# Hoja_principal_Sumo_2024.net
KiCad netlist of a schematic drawn in Altium Designer
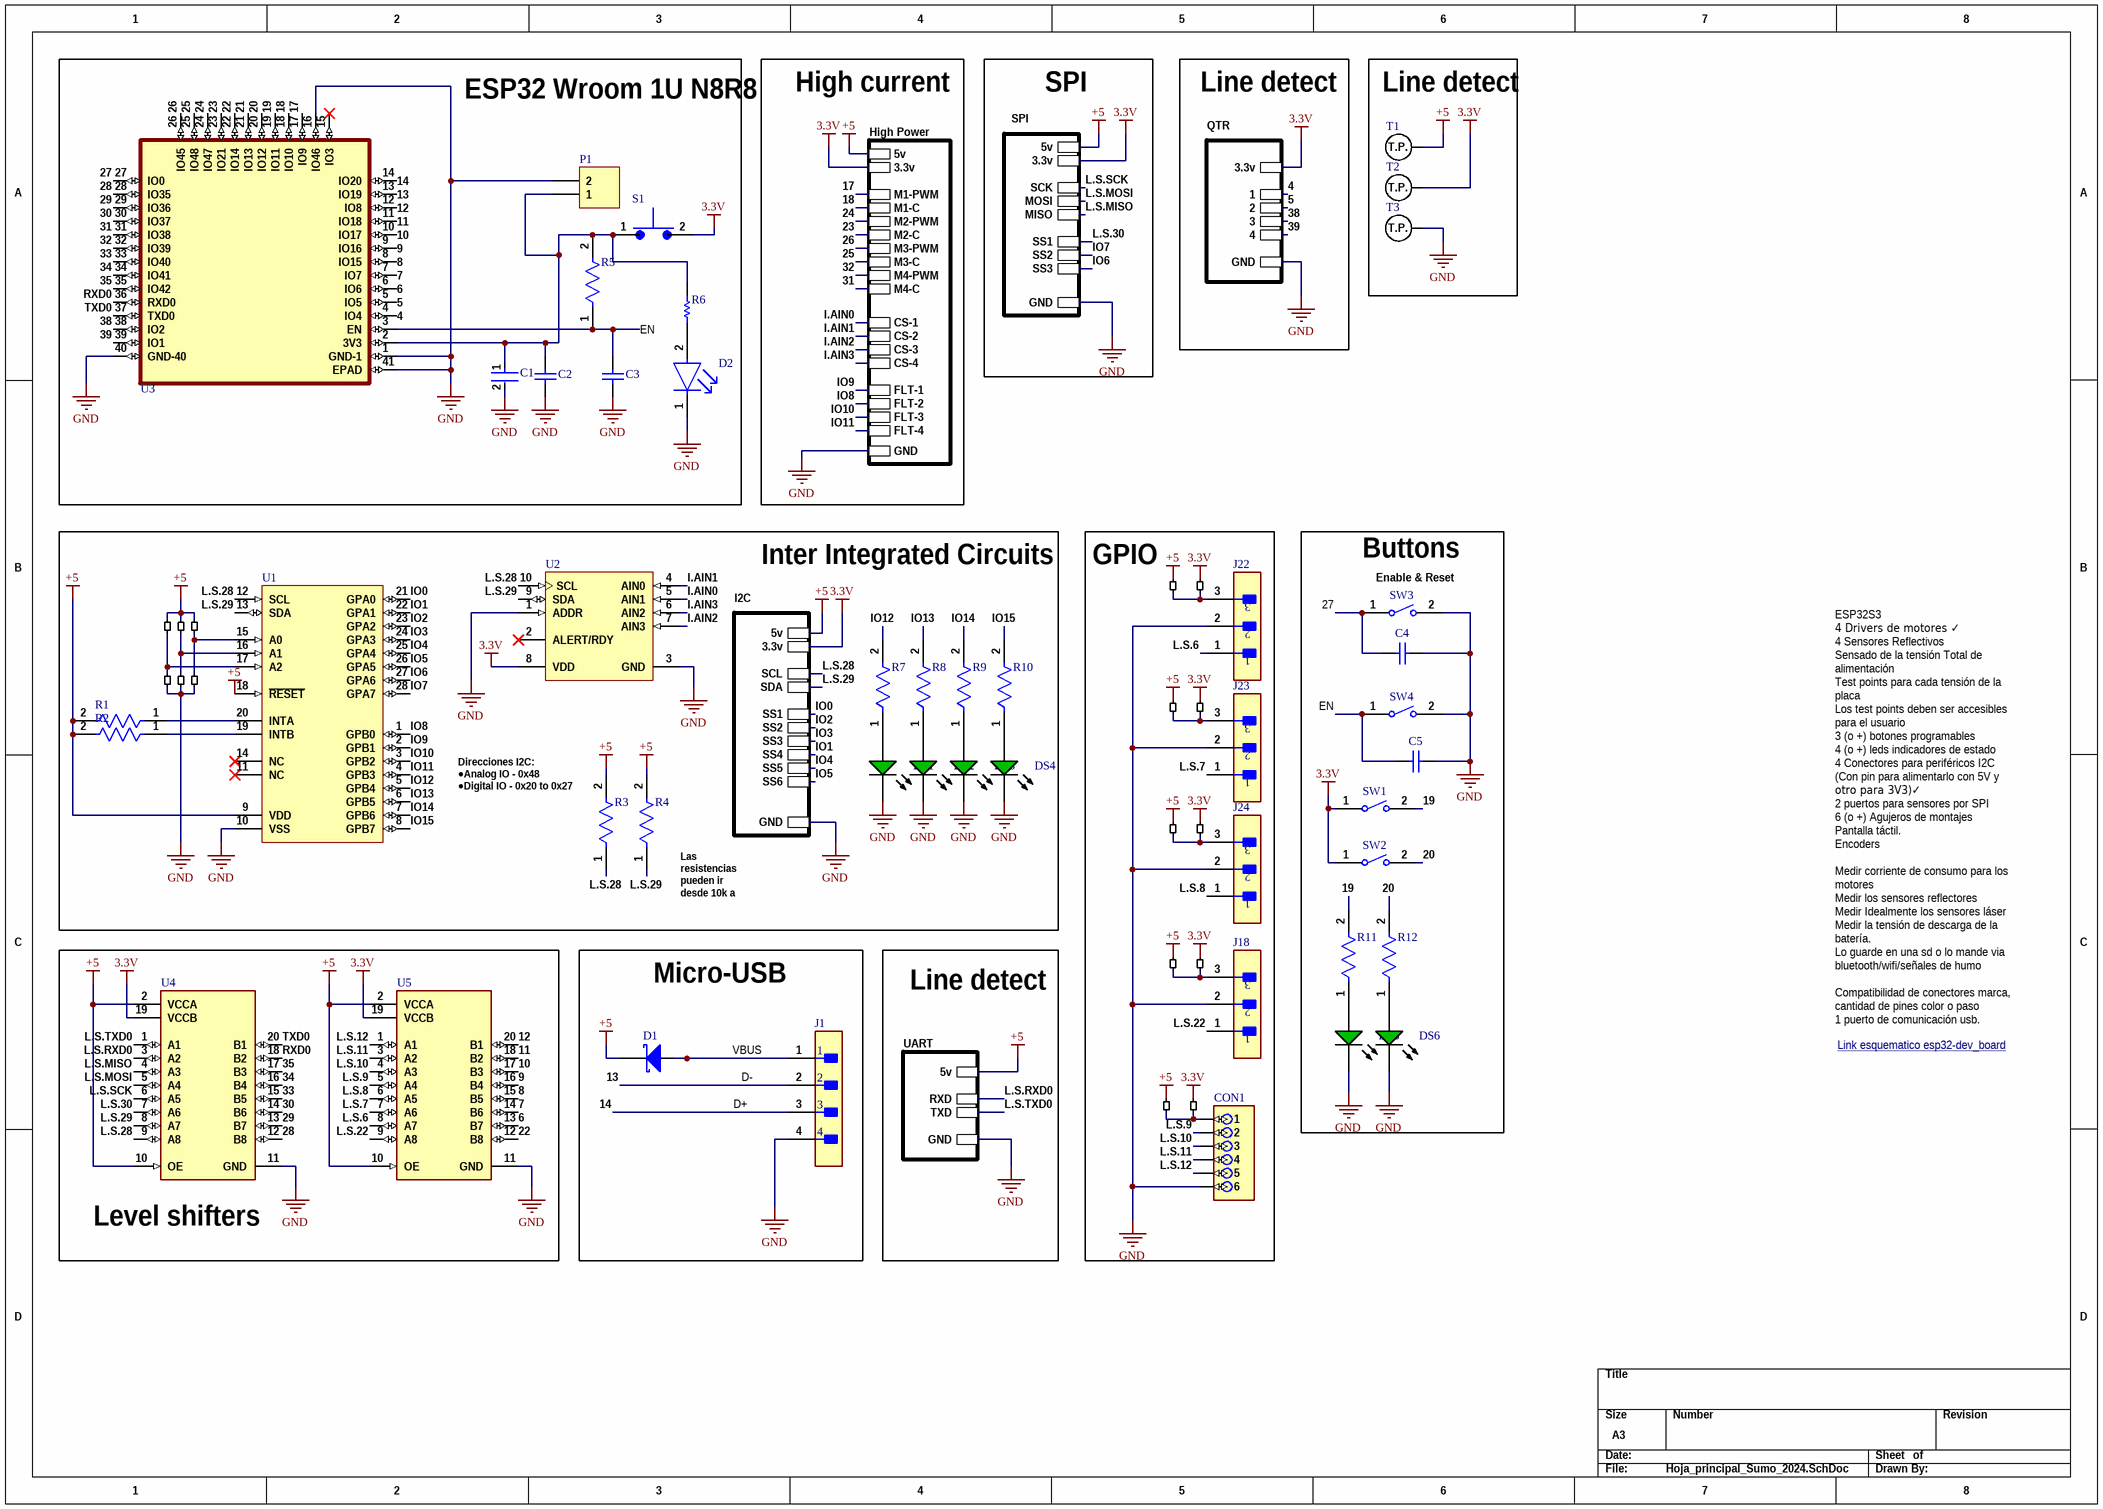
[diagram p0: Hoja_principal_Sumo_2024.SchDoc]

(export (version "E")
  (design (tool "Eeschema 10.0.6"))
  (components
    (comp (ref "C1")
      (value "TMK212BBJ106KG-T")
      (footprint "FP-0805-L_2_0_0_2-W_1_25-MFG")
      (description "Multilayer Ceramic Capacitor 10uF 25V X5R 10% SMD 0805 T/R")
      (fields (field (name "VOLTAGE") "16V") (field (name "TOLERANCE") "10%"))
      (libsource (lib "Altium Content Vault") (part "02cd4be3c70576c341d710602a673aa"))
    )
    (comp (ref "C2")
      (value "GRM21BR71H104KA01L")
      (footprint "CAPC2013X135X45ML10T25")
      (description "Chip Capacitor, 0.1 uF, +/- 10%, 50 V, -55 to 125 degC, 0805 (2012 Metric), RoHS, Tape and Reel")
      (fields (field (name "VOLTAGE") "50V") (field (name "TOLERANCE") "10%"))
      (libsource (lib "Altium Content Vault") (part "CAP-NP-2"))
    )
    (comp (ref "C3")
      (value "C0805C105K4PACTU")
      (footprint "CAPC2013X145X50LL20T25")
      (fields (field (name "MANUFACTURER") "Kemet"))
      (libsource (lib "Altium Content Vault") (part "CAP"))
    )
    (comp (ref "C4")
      (value "GRM21BR71H104KA01L")
      (footprint "CAPC2013X135X45ML10T25")
      (description "Chip Capacitor, 0.1 uF, +/- 10%, 50 V, -55 to 125 degC, 0805 (2012 Metric), RoHS, Tape and Reel")
      (fields (field (name "VOLTAGE") "50V") (field (name "TOLERANCE") "10%"))
      (libsource (lib "Altium Content Vault") (part "CAP-NP-2"))
    )
    (comp (ref "C5")
      (value "GRM21BR71H104KA01L")
      (footprint "CAPC2013X135X45ML10T25")
      (description "Chip Capacitor, 0.1 uF, +/- 10%, 50 V, -55 to 125 degC, 0805 (2012 Metric), RoHS, Tape and Reel")
      (fields (field (name "VOLTAGE") "50V") (field (name "TOLERANCE") "10%"))
      (libsource (lib "Altium Content Vault") (part "CAP-NP-2"))
    )
    (comp (ref "CON1")
      (value "B6B-ZR")
      (footprint "B6B-ZR")
      (description "Connector Header Surface Mount 6 position 0.059 (1.50mm)")
      (fields (field (name "MF") "JST"))
      (libsource (lib "B6B-ZR") (part "B6B-ZR"))
    )
    (comp (ref "D1")
      (value "BAS3010A03WE6327HTSA1")
      (footprint "INF-SOD323_V")
      (description "Medium Power AF Schottky Diode, 0.41 V, 1 A, -65 to 125 degC, 2-Pin SOD323, RoHS, Tape and Reel")
      (fields (field (name "MANUFACTURER") "Infineon"))
      (libsource (lib "Altium Content Vault") (part "DSKY-KA-2"))
    )
    (comp (ref "D2")
      (value "APHCM2012SYCK-F01")
      (footprint "FP-APHCM2012SYCK-F01-MFG")
      (description "LED YELLOW CLEAR CHIP SMD")
      (libsource (lib "Altium Content Vault") (part "8706943c75ba83719d021d2fdc84c58"))
    )
    (comp (ref "DS1")
      (value "HSMG-C170")
      (footprint "AVAG-HSMX-C170_V")
      (description "Chip LED, Green, 2.2 V, -40 to 85 degC, 2-Pin SMD, Pb-Free, Tape and Reel")
      (fields (field (name "MANUFACTURER") "Avago"))
      (libsource (lib "Altium Content Vault") (part "LED_GREEN_A1K2-2"))
    )
    (comp (ref "DS2")
      (value "HSMG-C170")
      (footprint "AVAG-HSMX-C170_V")
      (description "Chip LED, Green, 2.2 V, -40 to 85 degC, 2-Pin SMD, Pb-Free, Tape and Reel")
      (fields (field (name "MANUFACTURER") "Avago"))
      (libsource (lib "Altium Content Vault") (part "LED_GREEN_A1K2-2"))
    )
    (comp (ref "DS3")
      (value "HSMG-C170")
      (footprint "AVAG-HSMX-C170_V")
      (description "Chip LED, Green, 2.2 V, -40 to 85 degC, 2-Pin SMD, Pb-Free, Tape and Reel")
      (fields (field (name "MANUFACTURER") "Avago"))
      (libsource (lib "Altium Content Vault") (part "LED_GREEN_A1K2-2"))
    )
    (comp (ref "DS4")
      (value "HSMG-C170")
      (footprint "AVAG-HSMX-C170_V")
      (description "Chip LED, Green, 2.2 V, -40 to 85 degC, 2-Pin SMD, Pb-Free, Tape and Reel")
      (fields (field (name "MANUFACTURER") "Avago"))
      (libsource (lib "Altium Content Vault") (part "LED_GREEN_A1K2-2"))
    )
    (comp (ref "DS5")
      (value "HSMG-C170")
      (footprint "AVAG-HSMX-C170_V")
      (description "Chip LED, Green, 2.2 V, -40 to 85 degC, 2-Pin SMD, Pb-Free, Tape and Reel")
      (fields (field (name "MANUFACTURER") "Avago"))
      (libsource (lib "Altium Content Vault") (part "LED_GREEN_A1K2-2"))
    )
    (comp (ref "DS6")
      (value "HSMG-C170")
      (footprint "AVAG-HSMX-C170_V")
      (description "Chip LED, Green, 2.2 V, -40 to 85 degC, 2-Pin SMD, Pb-Free, Tape and Reel")
      (fields (field (name "MANUFACTURER") "Avago"))
      (libsource (lib "Altium Content Vault") (part "LED_GREEN_A1K2-2"))
    )
    (comp (ref "J1")
      (value "B4B-ZR(LF)(SN)")
      (footprint "FP-B4B-ZR_LF_SN-MFG")
      (description "CONN HEADER VERT 4POS 1.5MM")
      (libsource (lib "Altium Content Vault") (part "299a8cea1bdcbc3624fe62c390fa72c"))
    )
    (comp (ref "J18")
      (value "B3B-ZR(LF)(SN)")
      (footprint "FP-B3B-ZR_LF_SN-MFG")
      (description "CONN HEADER VERT 3POS 1.5MM")
      (libsource (lib "Altium Content Vault") (part "0d3f023dd272f625e17a2be33dea85f"))
    )
    (comp (ref "J22")
      (value "B3B-ZR(LF)(SN)")
      (footprint "FP-B3B-ZR_LF_SN-MFG")
      (description "CONN HEADER VERT 3POS 1.5MM")
      (libsource (lib "Altium Content Vault") (part "0d3f023dd272f625e17a2be33dea85f"))
    )
    (comp (ref "J23")
      (value "B3B-ZR(LF)(SN)")
      (footprint "FP-B3B-ZR_LF_SN-MFG")
      (description "CONN HEADER VERT 3POS 1.5MM")
      (libsource (lib "Altium Content Vault") (part "0d3f023dd272f625e17a2be33dea85f"))
    )
    (comp (ref "J24")
      (value "B3B-ZR(LF)(SN)")
      (footprint "FP-B3B-ZR_LF_SN-MFG")
      (description "CONN HEADER VERT 3POS 1.5MM")
      (libsource (lib "Altium Content Vault") (part "0d3f023dd272f625e17a2be33dea85f"))
    )
    (comp (ref "P1")
      (value "Header 2")
      (footprint "HDR1X2")
      (description "Header, 2-Pin")
      (fields (field (name "PUBLISHER") "Altium Limited"))
      (libsource (lib "Miscellaneous Connectors") (part "Header 2"))
    )
    (comp (ref "R1")
      (value "CRCW080510K0FKEA")
      (footprint "FP-CRCW0805-e3-IPC_A")
      (description "RES Thick Film, 10kΩ, 1%, 0.125W, 100ppm/°C, 0805")
      (fields (field (name "TOLERANCE") "1%"))
      (libsource (lib "Altium Content Vault") (part "1029c3af85768c4190bb7ad29bc67b5"))
    )
    (comp (ref "R2")
      (value "CRCW080510K0FKEA")
      (footprint "FP-CRCW0805-e3-IPC_A")
      (description "RES Thick Film, 10kΩ, 1%, 0.125W, 100ppm/°C, 0805")
      (fields (field (name "TOLERANCE") "1%"))
      (libsource (lib "Altium Content Vault") (part "1029c3af85768c4190bb7ad29bc67b5"))
    )
    (comp (ref "R3")
      (value "CRCW080510K0FKEA")
      (footprint "FP-CRCW0805-e3-IPC_A")
      (description "RES Thick Film, 10kΩ, 1%, 0.125W, 100ppm/°C, 0805")
      (fields (field (name "TOLERANCE") "1%"))
      (libsource (lib "Altium Content Vault") (part "1029c3af85768c4190bb7ad29bc67b5"))
    )
    (comp (ref "R4")
      (value "CRCW080510K0FKEA")
      (footprint "FP-CRCW0805-e3-IPC_A")
      (description "RES Thick Film, 10kΩ, 1%, 0.125W, 100ppm/°C, 0805")
      (fields (field (name "TOLERANCE") "1%"))
      (libsource (lib "Altium Content Vault") (part "1029c3af85768c4190bb7ad29bc67b5"))
    )
    (comp (ref "R5")
      (value "CRCW080510K0FKEA")
      (footprint "FP-CRCW0805-e3-IPC_A")
      (description "RES Thick Film, 10kΩ, 1%, 0.125W, 100ppm/°C, 0805")
      (fields (field (name "TOLERANCE") "1%"))
      (libsource (lib "Altium Content Vault") (part "1029c3af85768c4190bb7ad29bc67b5"))
    )
    (comp (ref "R6")
      (value "CRCW0805680RFKEA")
      (footprint "RESC2013X50X30NL20T20")
      (fields (field (name "MANUFACTURER") "Vishay Dale"))
      (libsource (lib "Altium Content Vault") (part "RES"))
    )
    (comp (ref "R7")
      (value "CRCW0805390RFKEA")
      (footprint "FP-CRCW0805-e3-IPC_B")
      (description "RES Thick Film, 390Ω, 1%, 0.125W, 100ppm/°C, 0805")
      (fields (field (name "TOLERANCE") "1%"))
      (libsource (lib "Altium Content Vault") (part "1029c3af85768c4190bb7ad29bc67b5"))
    )
    (comp (ref "R8")
      (value "CRCW0805390RFKEA")
      (footprint "FP-CRCW0805-e3-IPC_B")
      (description "RES Thick Film, 390Ω, 1%, 0.125W, 100ppm/°C, 0805")
      (fields (field (name "TOLERANCE") "1%"))
      (libsource (lib "Altium Content Vault") (part "1029c3af85768c4190bb7ad29bc67b5"))
    )
    (comp (ref "R9")
      (value "CRCW0805390RFKEA")
      (footprint "FP-CRCW0805-e3-IPC_B")
      (description "RES Thick Film, 390Ω, 1%, 0.125W, 100ppm/°C, 0805")
      (fields (field (name "TOLERANCE") "1%"))
      (libsource (lib "Altium Content Vault") (part "1029c3af85768c4190bb7ad29bc67b5"))
    )
    (comp (ref "R10")
      (value "CRCW0805390RFKEA")
      (footprint "FP-CRCW0805-e3-IPC_B")
      (description "RES Thick Film, 390Ω, 1%, 0.125W, 100ppm/°C, 0805")
      (fields (field (name "TOLERANCE") "1%"))
      (libsource (lib "Altium Content Vault") (part "1029c3af85768c4190bb7ad29bc67b5"))
    )
    (comp (ref "R11")
      (value "CRCW0805390RFKEA")
      (footprint "FP-CRCW0805-e3-IPC_B")
      (description "RES Thick Film, 390Ω, 1%, 0.125W, 100ppm/°C, 0805")
      (fields (field (name "TOLERANCE") "1%"))
      (libsource (lib "Altium Content Vault") (part "1029c3af85768c4190bb7ad29bc67b5"))
    )
    (comp (ref "R12")
      (value "CRCW0805390RFKEA")
      (footprint "FP-CRCW0805-e3-IPC_B")
      (description "RES Thick Film, 390Ω, 1%, 0.125W, 100ppm/°C, 0805")
      (fields (field (name "TOLERANCE") "1%"))
      (libsource (lib "Altium Content Vault") (part "1029c3af85768c4190bb7ad29bc67b5"))
    )
    (comp (ref "S1")
      (value "TS10-63-26-BE-250-SMT-TR")
      (footprint "Switch SMD")
      (libsource (lib "TS10-63-26-BE-250-SMT-TR") (part "TS10-63-26-BE-250-SMT-TR"))
    )
    (comp (ref "SW1")
      (value "FSMSMTR")
      (footprint "TECO-FSMSMTR_V")
      (description "FSMSM Push Button Switch, 50 mA, -35 to 85 degC, 2-Pin SMD, RoHS, Tape and Reel")
      (fields (field (name "MANUFACTURER") "TE Connectivity"))
      (libsource (lib "Altium Content Vault") (part "SW-SPST-2_C"))
    )
    (comp (ref "SW2")
      (value "FSMSMTR")
      (footprint "TECO-FSMSMTR_V")
      (description "FSMSM Push Button Switch, 50 mA, -35 to 85 degC, 2-Pin SMD, RoHS, Tape and Reel")
      (fields (field (name "MANUFACTURER") "TE Connectivity"))
      (libsource (lib "Altium Content Vault") (part "SW-SPST-2_C"))
    )
    (comp (ref "SW3")
      (value "FSMSMTR")
      (footprint "TECO-FSMSMTR_V")
      (description "FSMSM Push Button Switch, 50 mA, -35 to 85 degC, 2-Pin SMD, RoHS, Tape and Reel")
      (fields (field (name "MANUFACTURER") "TE Connectivity"))
      (libsource (lib "Altium Content Vault") (part "SW-SPST-2_C"))
    )
    (comp (ref "SW4")
      (value "FSMSMTR")
      (footprint "TECO-FSMSMTR_V")
      (description "FSMSM Push Button Switch, 50 mA, -35 to 85 degC, 2-Pin SMD, RoHS, Tape and Reel")
      (fields (field (name "MANUFACTURER") "TE Connectivity"))
      (libsource (lib "Altium Content Vault") (part "SW-SPST-2_C"))
    )
    (comp (ref "T1")
      (value "Test point")
      (footprint "Testpoint")
      (libsource (lib "Schlib2") (part "Test point"))
    )
    (comp (ref "T2")
      (value "Test point")
      (footprint "Testpoint")
      (libsource (lib "Schlib2") (part "Test point"))
    )
    (comp (ref "T3")
      (value "Test point")
      (footprint "Testpoint")
      (libsource (lib "Schlib2") (part "Test point"))
    )
    (comp (ref "U1")
      (value "MCP23017-E/SS")
      (footprint "SSOP-SS28_L")
      (description "16-Bit I/O Expander with Serial Interface, 28-Pin SSOP, Extended Temperature")
      (libsource (lib "Altium Content Vault") (part "PR-BUSIC-MCP23017-28"))
    )
    (comp (ref "U2")
      (value "ADS1115IDGST")
      (footprint "TI-DGS10_N")
      (fields (field (name "MANUFACTURER") "Texas Instruments"))
      (libsource (lib "Altium Content Vault") (part "TI-ADS1015_1115-10"))
    )
    (comp (ref "U3")
      (value "ESP32-S3-WROOM-1 N8R8")
      (footprint "PCBComponent_1")
      (description "SMD MODULE, ESP32-S3R8 WITH 8 MB")
      (fields (field (name "MF") "Espressif Systems") (field (name "MP") "ESP32-S3-WROOM-1"))
      (libsource (lib "ESP32-S3-WROOM-1") (part "ESP32-S3-WROOM-1"))
    )
    (comp (ref "U4")
      (value "TXS0108EQPWRQ1")
      (footprint "FP-PW0020A-MFG")
      (description "IC TRNSLTR BIDIRECTIONAL 20TSSOP")
      (fields
        (field (name "OCTOPART") "https://octopart.com/txs0108eqpwrq1-texas+instruments-59160487")
        (field (name "MANUFACTURER") "Texas Instruments")
      )
      (libsource (lib "Altium Content Vault") (part "b852cf3f2c97e4a3d4172ee3f19d589"))
    )
    (comp (ref "U5")
      (value "TXS0108EQPWRQ1")
      (footprint "FP-PW0020A-MFG")
      (description "IC TRNSLTR BIDIRECTIONAL 20TSSOP")
      (fields
        (field (name "OCTOPART") "https://octopart.com/txs0108eqpwrq1-texas+instruments-59160487")
        (field (name "MANUFACTURER") "Texas Instruments")
      )
      (libsource (lib "Altium Content Vault") (part "b852cf3f2c97e4a3d4172ee3f19d589"))
    )
    (comp (ref "W1") (value "Jumper") (footprint "Jumper Mini") (libsource (lib "Schlib1") (part "Jumper")))
    (comp (ref "W2") (value "Jumper") (footprint "Jumper Mini") (libsource (lib "Schlib1") (part "Jumper")))
    (comp (ref "W3") (value "Jumper") (footprint "Jumper Mini") (libsource (lib "Schlib1") (part "Jumper")))
    (comp (ref "W4") (value "Jumper") (footprint "Jumper Mini") (libsource (lib "Schlib1") (part "Jumper")))
    (comp (ref "W5") (value "Jumper") (footprint "Jumper Mini") (libsource (lib "Schlib1") (part "Jumper")))
    (comp (ref "W6") (value "Jumper") (footprint "Jumper Mini") (libsource (lib "Schlib1") (part "Jumper")))
    (comp (ref "W7") (value "Jumper") (footprint "Jumper Mid") (libsource (lib "Schlib1") (part "Jumper")))
    (comp (ref "W8") (value "Jumper") (footprint "Jumper Mid") (libsource (lib "Schlib1") (part "Jumper")))
    (comp (ref "W9") (value "Jumper") (footprint "Jumper Mid") (libsource (lib "Schlib1") (part "Jumper")))
    (comp (ref "W10") (value "Jumper") (footprint "Jumper Mid") (libsource (lib "Schlib1") (part "Jumper")))
    (comp (ref "W11") (value "Jumper") (footprint "Jumper Mid") (libsource (lib "Schlib1") (part "Jumper")))
    (comp (ref "W12") (value "Jumper") (footprint "Jumper Mid") (libsource (lib "Schlib1") (part "Jumper")))
    (comp (ref "W13") (value "Jumper") (footprint "Jumper Mid") (libsource (lib "Schlib1") (part "Jumper")))
    (comp (ref "W14") (value "Jumper") (footprint "Jumper Mid") (libsource (lib "Schlib1") (part "Jumper")))
    (comp (ref "W27") (value "Jumper") (footprint "Jumper Mid") (libsource (lib "Schlib1") (part "Jumper")))
    (comp (ref "W28") (value "Jumper") (footprint "Jumper Mid") (libsource (lib "Schlib1") (part "Jumper")))
  )
  (nets
    (net (code "1") (name "+5") (class "Default")
      (node (ref "D1") (pin "1") (pinfunction "K_1") (pintype "passive"))
      (node (ref "R1") (pin "2") (pinfunction "2_2") (pintype "passive"))
      (node (ref "R2") (pin "2") (pinfunction "2_2") (pintype "passive"))
      (node (ref "R3") (pin "2") (pinfunction "2_2") (pintype "passive"))
      (node (ref "R4") (pin "2") (pinfunction "2_2") (pintype "passive"))
      (node (ref "T1") (pin "1") (pinfunction "T.P._1") (pintype "passive"))
      (node (ref "U1") (pin "18") (pinfunction "~{RESET}_18") (pintype "input"))
      (node (ref "U1") (pin "9") (pinfunction "VDD_9") (pintype "power_in"))
      (node (ref "U4") (pin "10") (pinfunction "OE_10") (pintype "input"))
      (node (ref "U4") (pin "2") (pinfunction "VCCA_2") (pintype "power_in"))
      (node (ref "U5") (pin "10") (pinfunction "OE_10") (pintype "input"))
      (node (ref "U5") (pin "2") (pinfunction "VCCA_2") (pintype "power_in"))
      (node (ref "W1") (pin "2") (pinfunction "2_2") (pintype "passive"))
      (node (ref "W10") (pin "2") (pinfunction "2_2") (pintype "passive"))
      (node (ref "W27") (pin "2") (pinfunction "2_2") (pintype "passive"))
      (node (ref "W3") (pin "2") (pinfunction "2_2") (pintype "passive"))
      (node (ref "W5") (pin "2") (pinfunction "2_2") (pintype "passive"))
      (node (ref "W7") (pin "2") (pinfunction "2_2") (pintype "passive"))
      (node (ref "W8") (pin "2") (pinfunction "2_2") (pintype "passive"))
      (node (ref "W9") (pin "2") (pinfunction "2_2") (pintype "passive"))
    )
    (net (code "2") (name "/4") (class "Default")
      (node (ref "U3") (pin "4") (pinfunction "IO4_4") (pintype "bidirectional"))
    )
    (net (code "3") (name "/5") (class "Default")
      (node (ref "U3") (pin "5") (pinfunction "IO5_5") (pintype "bidirectional"))
    )
    (net (code "4") (name "/6") (class "Default")
      (node (ref "U3") (pin "6") (pinfunction "IO6_6") (pintype "bidirectional"))
      (node (ref "U5") (pin "13") (pinfunction "B7_13") (pintype "bidirectional"))
    )
    (net (code "5") (name "/7") (class "Default")
      (node (ref "U3") (pin "7") (pinfunction "IO7_7") (pintype "bidirectional"))
      (node (ref "U5") (pin "14") (pinfunction "B6_14") (pintype "bidirectional"))
    )
    (net (code "6") (name "/8") (class "Default")
      (node (ref "U3") (pin "8") (pinfunction "IO15_8") (pintype "bidirectional"))
      (node (ref "U5") (pin "15") (pinfunction "B5_15") (pintype "bidirectional"))
    )
    (net (code "7") (name "/9") (class "Default")
      (node (ref "U3") (pin "9") (pinfunction "IO16_9") (pintype "bidirectional"))
      (node (ref "U5") (pin "16") (pinfunction "B4_16") (pintype "bidirectional"))
    )
    (net (code "8") (name "/10") (class "Default")
      (node (ref "U3") (pin "10") (pinfunction "IO17_10") (pintype "bidirectional"))
      (node (ref "U5") (pin "17") (pinfunction "B3_17") (pintype "bidirectional"))
    )
    (net (code "9") (name "/11") (class "Default")
      (node (ref "U3") (pin "11") (pinfunction "IO18_11") (pintype "bidirectional"))
      (node (ref "U5") (pin "18") (pinfunction "B2_18") (pintype "bidirectional"))
    )
    (net (code "10") (name "/12") (class "Default")
      (node (ref "U3") (pin "12") (pinfunction "IO8_12") (pintype "bidirectional"))
      (node (ref "U5") (pin "20") (pinfunction "B1_20") (pintype "bidirectional"))
    )
    (net (code "11") (name "/13") (class "Default")
      (node (ref "J1") (pin "2") (pinfunction "2_2") (pintype "passive"))
      (node (ref "U3") (pin "13") (pinfunction "IO19_13") (pintype "bidirectional"))
    )
    (net (code "12") (name "/14") (class "Default")
      (node (ref "J1") (pin "3") (pinfunction "3_3") (pintype "passive"))
      (node (ref "U3") (pin "14") (pinfunction "IO20_14") (pintype "bidirectional"))
    )
    (net (code "13") (name "/17") (class "Default")
      (node (ref "U3") (pin "17") (pinfunction "IO9_17") (pintype "bidirectional"))
    )
    (net (code "14") (name "/18") (class "Default")
      (node (ref "U3") (pin "18") (pinfunction "IO10_18") (pintype "bidirectional"))
    )
    (net (code "15") (name "/19") (class "Default")
      (node (ref "R11") (pin "2") (pinfunction "2_2") (pintype "passive"))
      (node (ref "SW1") (pin "2") (pinfunction "2_2") (pintype "passive"))
      (node (ref "U3") (pin "19") (pinfunction "IO11_19") (pintype "bidirectional"))
    )
    (net (code "16") (name "/20") (class "Default")
      (node (ref "R12") (pin "2") (pinfunction "2_2") (pintype "passive"))
      (node (ref "SW2") (pin "2") (pinfunction "2_2") (pintype "passive"))
      (node (ref "U3") (pin "20") (pinfunction "IO12_20") (pintype "bidirectional"))
    )
    (net (code "17") (name "/21") (class "Default")
      (node (ref "U3") (pin "21") (pinfunction "IO13_21") (pintype "bidirectional"))
    )
    (net (code "18") (name "/22") (class "Default")
      (node (ref "U3") (pin "22") (pinfunction "IO14_22") (pintype "bidirectional"))
      (node (ref "U5") (pin "12") (pinfunction "B8_12") (pintype "bidirectional"))
    )
    (net (code "19") (name "/23") (class "Default")
      (node (ref "U3") (pin "23") (pinfunction "IO21_23") (pintype "bidirectional"))
    )
    (net (code "20") (name "/24") (class "Default")
      (node (ref "U3") (pin "24") (pinfunction "IO47_24") (pintype "bidirectional"))
    )
    (net (code "21") (name "/25") (class "Default")
      (node (ref "U3") (pin "25") (pinfunction "IO48_25") (pintype "bidirectional"))
    )
    (net (code "22") (name "/26") (class "Default")
      (node (ref "U3") (pin "26") (pinfunction "IO45_26") (pintype "bidirectional"))
    )
    (net (code "23") (name "/27") (class "Default")
      (node (ref "C4") (pin "2") (pinfunction "2_2") (pintype "passive"))
      (node (ref "SW3") (pin "1") (pinfunction "1_1") (pintype "passive"))
      (node (ref "U3") (pin "27") (pinfunction "IO0_27") (pintype "bidirectional"))
    )
    (net (code "24") (name "/28") (class "Default")
      (node (ref "U3") (pin "28") (pinfunction "IO35_28") (pintype "bidirectional"))
      (node (ref "U4") (pin "12") (pinfunction "B8_12") (pintype "bidirectional"))
    )
    (net (code "25") (name "/29") (class "Default")
      (node (ref "U3") (pin "29") (pinfunction "IO36_29") (pintype "bidirectional"))
      (node (ref "U4") (pin "13") (pinfunction "B7_13") (pintype "bidirectional"))
    )
    (net (code "26") (name "/30") (class "Default")
      (node (ref "U3") (pin "30") (pinfunction "IO37_30") (pintype "bidirectional"))
      (node (ref "U4") (pin "14") (pinfunction "B6_14") (pintype "bidirectional"))
    )
    (net (code "27") (name "/31") (class "Default")
      (node (ref "U3") (pin "31") (pinfunction "IO38_31") (pintype "bidirectional"))
    )
    (net (code "28") (name "/32") (class "Default")
      (node (ref "U3") (pin "32") (pinfunction "IO39_32") (pintype "bidirectional"))
    )
    (net (code "29") (name "/33") (class "Default")
      (node (ref "U3") (pin "33") (pinfunction "IO40_33") (pintype "bidirectional"))
      (node (ref "U4") (pin "15") (pinfunction "B5_15") (pintype "bidirectional"))
    )
    (net (code "30") (name "/34") (class "Default")
      (node (ref "U3") (pin "34") (pinfunction "IO41_34") (pintype "bidirectional"))
      (node (ref "U4") (pin "16") (pinfunction "B4_16") (pintype "bidirectional"))
    )
    (net (code "31") (name "/35") (class "Default")
      (node (ref "U3") (pin "35") (pinfunction "IO42_35") (pintype "bidirectional"))
      (node (ref "U4") (pin "17") (pinfunction "B3_17") (pintype "bidirectional"))
    )
    (net (code "32") (name "/38") (class "Default")
      (node (ref "U3") (pin "38") (pinfunction "IO2_38") (pintype "bidirectional"))
    )
    (net (code "33") (name "/39") (class "Default")
      (node (ref "U3") (pin "39") (pinfunction "IO1_39") (pintype "bidirectional"))
    )
    (net (code "34") (name "/EN") (class "Default")
      (node (ref "C3") (pin "2") (pinfunction "2_2") (pintype "passive"))
      (node (ref "C5") (pin "2") (pinfunction "2_2") (pintype "passive"))
      (node (ref "R5") (pin "1") (pinfunction "1_1") (pintype "passive"))
      (node (ref "SW4") (pin "1") (pinfunction "1_1") (pintype "passive"))
      (node (ref "U3") (pin "3") (pinfunction "EN_3") (pintype "bidirectional"))
    )
    (net (code "35") (name "/I.AIN0") (class "Default")
      (node (ref "U2") (pin "5") (pinfunction "AIN1_5") (pintype "input"))
    )
    (net (code "36") (name "/I.AIN1") (class "Default")
      (node (ref "U2") (pin "4") (pinfunction "AIN0_4") (pintype "input"))
    )
    (net (code "37") (name "/I.AIN2") (class "Default")
      (node (ref "U2") (pin "7") (pinfunction "AIN3_7") (pintype "input"))
    )
    (net (code "38") (name "/I.AIN3") (class "Default")
      (node (ref "U2") (pin "6") (pinfunction "AIN2_6") (pintype "input"))
    )
    (net (code "39") (name "/IO0") (class "Default")
      (node (ref "U1") (pin "21") (pinfunction "GPA0_21") (pintype "bidirectional"))
    )
    (net (code "40") (name "/IO1") (class "Default")
      (node (ref "U1") (pin "22") (pinfunction "GPA1_22") (pintype "bidirectional"))
    )
    (net (code "41") (name "/IO2") (class "Default")
      (node (ref "U1") (pin "23") (pinfunction "GPA2_23") (pintype "bidirectional"))
    )
    (net (code "42") (name "/IO3") (class "Default")
      (node (ref "U1") (pin "24") (pinfunction "GPA3_24") (pintype "bidirectional"))
    )
    (net (code "43") (name "/IO4") (class "Default")
      (node (ref "U1") (pin "25") (pinfunction "GPA4_25") (pintype "bidirectional"))
    )
    (net (code "44") (name "/IO5") (class "Default")
      (node (ref "U1") (pin "26") (pinfunction "GPA5_26") (pintype "bidirectional"))
    )
    (net (code "45") (name "/IO6") (class "Default")
      (node (ref "U1") (pin "27") (pinfunction "GPA6_27") (pintype "bidirectional"))
    )
    (net (code "46") (name "/IO7") (class "Default")
      (node (ref "U1") (pin "28") (pinfunction "GPA7_28") (pintype "bidirectional"))
    )
    (net (code "47") (name "/IO8") (class "Default")
      (node (ref "U1") (pin "1") (pinfunction "GPB0_1") (pintype "bidirectional"))
    )
    (net (code "48") (name "/IO9") (class "Default")
      (node (ref "U1") (pin "2") (pinfunction "GPB1_2") (pintype "bidirectional"))
    )
    (net (code "49") (name "/IO10") (class "Default")
      (node (ref "U1") (pin "3") (pinfunction "GPB2_3") (pintype "bidirectional"))
    )
    (net (code "50") (name "/IO11") (class "Default")
      (node (ref "U1") (pin "4") (pinfunction "GPB3_4") (pintype "bidirectional"))
    )
    (net (code "51") (name "/IO12") (class "Default")
      (node (ref "R7") (pin "2") (pinfunction "2_2") (pintype "passive"))
      (node (ref "U1") (pin "5") (pinfunction "GPB4_5") (pintype "bidirectional"))
    )
    (net (code "52") (name "/IO13") (class "Default")
      (node (ref "R8") (pin "2") (pinfunction "2_2") (pintype "passive"))
      (node (ref "U1") (pin "6") (pinfunction "GPB5_6") (pintype "bidirectional"))
    )
    (net (code "53") (name "/IO14") (class "Default")
      (node (ref "R9") (pin "2") (pinfunction "2_2") (pintype "passive"))
      (node (ref "U1") (pin "7") (pinfunction "GPB6_7") (pintype "bidirectional"))
    )
    (net (code "54") (name "/IO15") (class "Default")
      (node (ref "R10") (pin "2") (pinfunction "2_2") (pintype "passive"))
      (node (ref "U1") (pin "8") (pinfunction "GPB7_8") (pintype "bidirectional"))
    )
    (net (code "55") (name "/L.S.6") (class "Default")
      (node (ref "J22") (pin "1") (pinfunction "1_1") (pintype "passive"))
      (node (ref "U5") (pin "8") (pinfunction "A7_8") (pintype "bidirectional"))
    )
    (net (code "56") (name "/L.S.7") (class "Default")
      (node (ref "J23") (pin "1") (pinfunction "1_1") (pintype "passive"))
      (node (ref "U5") (pin "7") (pinfunction "A6_7") (pintype "bidirectional"))
    )
    (net (code "57") (name "/L.S.8") (class "Default")
      (node (ref "J24") (pin "1") (pinfunction "1_1") (pintype "passive"))
      (node (ref "U5") (pin "6") (pinfunction "A5_6") (pintype "bidirectional"))
    )
    (net (code "58") (name "/L.S.9") (class "Default")
      (node (ref "CON1") (pin "2") (pinfunction "2_2") (pintype "bidirectional"))
      (node (ref "U5") (pin "5") (pinfunction "A4_5") (pintype "bidirectional"))
    )
    (net (code "59") (name "/L.S.10") (class "Default")
      (node (ref "CON1") (pin "3") (pinfunction "3_3") (pintype "bidirectional"))
      (node (ref "U5") (pin "4") (pinfunction "A3_4") (pintype "bidirectional"))
    )
    (net (code "60") (name "/L.S.11") (class "Default")
      (node (ref "CON1") (pin "4") (pinfunction "4_4") (pintype "bidirectional"))
      (node (ref "U5") (pin "3") (pinfunction "A2_3") (pintype "bidirectional"))
    )
    (net (code "61") (name "/L.S.12") (class "Default")
      (node (ref "CON1") (pin "5") (pinfunction "5_5") (pintype "bidirectional"))
      (node (ref "U5") (pin "1") (pinfunction "A1_1") (pintype "bidirectional"))
    )
    (net (code "62") (name "/L.S.22") (class "Default")
      (node (ref "J18") (pin "1") (pinfunction "1_1") (pintype "passive"))
      (node (ref "U5") (pin "9") (pinfunction "A8_9") (pintype "bidirectional"))
    )
    (net (code "63") (name "/L.S.28") (class "Default")
      (node (ref "R3") (pin "1") (pinfunction "1_1") (pintype "passive"))
      (node (ref "U1") (pin "12") (pinfunction "SCL_12") (pintype "input"))
      (node (ref "U2") (pin "10") (pinfunction "SCL_10") (pintype "input"))
      (node (ref "U4") (pin "9") (pinfunction "A8_9") (pintype "bidirectional"))
    )
    (net (code "64") (name "/L.S.29") (class "Default")
      (node (ref "R4") (pin "1") (pinfunction "1_1") (pintype "passive"))
      (node (ref "U1") (pin "13") (pinfunction "SDA_13") (pintype "bidirectional"))
      (node (ref "U2") (pin "9") (pinfunction "SDA_9") (pintype "bidirectional"))
      (node (ref "U4") (pin "8") (pinfunction "A7_8") (pintype "bidirectional"))
    )
    (net (code "65") (name "/L.S.30") (class "Default")
      (node (ref "U4") (pin "7") (pinfunction "A6_7") (pintype "bidirectional"))
    )
    (net (code "66") (name "/L.S.MISO") (class "Default")
      (node (ref "U4") (pin "4") (pinfunction "A3_4") (pintype "bidirectional"))
    )
    (net (code "67") (name "/L.S.MOSI") (class "Default")
      (node (ref "U4") (pin "5") (pinfunction "A4_5") (pintype "bidirectional"))
    )
    (net (code "68") (name "/L.S.RXD0") (class "Default")
      (node (ref "U4") (pin "3") (pinfunction "A2_3") (pintype "bidirectional"))
    )
    (net (code "69") (name "/L.S.SCK") (class "Default")
      (node (ref "U4") (pin "6") (pinfunction "A5_6") (pintype "bidirectional"))
    )
    (net (code "70") (name "/L.S.TXD0") (class "Default")
      (node (ref "U4") (pin "1") (pinfunction "A1_1") (pintype "bidirectional"))
    )
    (net (code "71") (name "/RXD0") (class "Default")
      (node (ref "U3") (pin "36") (pinfunction "RXD0_36") (pintype "bidirectional"))
      (node (ref "U4") (pin "18") (pinfunction "B2_18") (pintype "bidirectional"))
    )
    (net (code "72") (name "/TXD0") (class "Default")
      (node (ref "U3") (pin "37") (pinfunction "TXD0_37") (pintype "bidirectional"))
      (node (ref "U4") (pin "20") (pinfunction "B1_20") (pintype "bidirectional"))
    )
    (net (code "73") (name "/VBUS") (class "Default")
      (node (ref "D1") (pin "2") (pinfunction "A_2") (pintype "passive"))
      (node (ref "J1") (pin "1") (pinfunction "1_1") (pintype "passive"))
    )
    (net (code "74") (name "3.3V") (class "Default")
      (node (ref "S1") (pin "2") (pinfunction "2_2") (pintype "passive"))
      (node (ref "SW1") (pin "1") (pinfunction "1_1") (pintype "passive"))
      (node (ref "SW2") (pin "1") (pinfunction "1_1") (pintype "passive"))
      (node (ref "T2") (pin "1") (pinfunction "T.P._1") (pintype "passive"))
      (node (ref "U2") (pin "8") (pinfunction "VDD_8") (pintype "power_in"))
      (node (ref "U4") (pin "19") (pinfunction "VCCB_19") (pintype "power_in"))
      (node (ref "U5") (pin "19") (pinfunction "VCCB_19") (pintype "power_in"))
      (node (ref "W11") (pin "2") (pinfunction "2_2") (pintype "passive"))
      (node (ref "W12") (pin "2") (pinfunction "2_2") (pintype "passive"))
      (node (ref "W13") (pin "2") (pinfunction "2_2") (pintype "passive"))
      (node (ref "W14") (pin "2") (pinfunction "2_2") (pintype "passive"))
      (node (ref "W28") (pin "2") (pinfunction "2_2") (pintype "passive"))
    )
    (net (code "75") (name "GND") (class "Default")
      (node (ref "C1") (pin "2") (pinfunction "2_2") (pintype "passive"))
      (node (ref "C2") (pin "2") (pinfunction "2_2") (pintype "passive"))
      (node (ref "C3") (pin "1") (pinfunction "1_1") (pintype "passive"))
      (node (ref "C4") (pin "1") (pinfunction "1_1") (pintype "passive"))
      (node (ref "C5") (pin "1") (pinfunction "1_1") (pintype "passive"))
      (node (ref "CON1") (pin "6") (pinfunction "6_6") (pintype "bidirectional"))
      (node (ref "D2") (pin "1") (pinfunction "C_1") (pintype "passive"))
      (node (ref "DS1") (pin "2") (pinfunction "K_2") (pintype "passive"))
      (node (ref "DS2") (pin "2") (pinfunction "K_2") (pintype "passive"))
      (node (ref "DS3") (pin "2") (pinfunction "K_2") (pintype "passive"))
      (node (ref "DS4") (pin "2") (pinfunction "K_2") (pintype "passive"))
      (node (ref "DS5") (pin "2") (pinfunction "K_2") (pintype "passive"))
      (node (ref "DS6") (pin "2") (pinfunction "K_2") (pintype "passive"))
      (node (ref "J1") (pin "4") (pinfunction "4_4") (pintype "passive"))
      (node (ref "J18") (pin "2") (pinfunction "2_2") (pintype "passive"))
      (node (ref "J22") (pin "2") (pinfunction "2_2") (pintype "passive"))
      (node (ref "J23") (pin "2") (pinfunction "2_2") (pintype "passive"))
      (node (ref "J24") (pin "2") (pinfunction "2_2") (pintype "passive"))
      (node (ref "P1") (pin "2") (pinfunction "2_2") (pintype "passive"))
      (node (ref "SW3") (pin "2") (pinfunction "2_2") (pintype "passive"))
      (node (ref "SW4") (pin "2") (pinfunction "2_2") (pintype "passive"))
      (node (ref "T3") (pin "1") (pinfunction "T.P._1") (pintype "passive"))
      (node (ref "U1") (pin "10") (pinfunction "VSS_10") (pintype "power_in"))
      (node (ref "U2") (pin "1") (pinfunction "ADDR_1") (pintype "input"))
      (node (ref "U2") (pin "3") (pinfunction "GND_3") (pintype "power_in"))
      (node (ref "U3") (pin "1") (pinfunction "GND-1_1") (pintype "bidirectional"))
      (node (ref "U3") (pin "16") (pinfunction "IO46_16") (pintype "bidirectional"))
      (node (ref "U3") (pin "40") (pinfunction "GND-40_40") (pintype "bidirectional"))
      (node (ref "U3") (pin "41") (pinfunction "EPAD_41") (pintype "bidirectional"))
      (node (ref "U4") (pin "11") (pinfunction "GND_11") (pintype "power_in"))
      (node (ref "U5") (pin "11") (pinfunction "GND_11") (pintype "power_in"))
      (node (ref "W2") (pin "1") (pinfunction "1_1") (pintype "passive"))
      (node (ref "W4") (pin "1") (pinfunction "1_1") (pintype "passive"))
      (node (ref "W6") (pin "1") (pinfunction "1_1") (pintype "passive"))
    )
    (net (code "76") (name "Net-(CON1-Pad1)") (class "Default")
      (node (ref "CON1") (pin "1") (pinfunction "1_1") (pintype "bidirectional"))
      (node (ref "W11") (pin "1") (pinfunction "1_1") (pintype "passive"))
      (node (ref "W7") (pin "1") (pinfunction "1_1") (pintype "passive"))
    )
    (net (code "77") (name "Net-(D2-A)") (class "Default")
      (node (ref "D2") (pin "2") (pinfunction "A_2") (pintype "passive"))
      (node (ref "R6") (pin "1") (pinfunction "1_1") (pintype "passive"))
    )
    (net (code "78") (name "Net-(DS1-A)") (class "Default")
      (node (ref "DS1") (pin "1") (pinfunction "A_1") (pintype "passive"))
      (node (ref "R7") (pin "1") (pinfunction "1_1") (pintype "passive"))
    )
    (net (code "79") (name "Net-(DS2-A)") (class "Default")
      (node (ref "DS2") (pin "1") (pinfunction "A_1") (pintype "passive"))
      (node (ref "R8") (pin "1") (pinfunction "1_1") (pintype "passive"))
    )
    (net (code "80") (name "Net-(DS3-A)") (class "Default")
      (node (ref "DS3") (pin "1") (pinfunction "A_1") (pintype "passive"))
      (node (ref "R9") (pin "1") (pinfunction "1_1") (pintype "passive"))
    )
    (net (code "81") (name "Net-(DS4-A)") (class "Default")
      (node (ref "DS4") (pin "1") (pinfunction "A_1") (pintype "passive"))
      (node (ref "R10") (pin "1") (pinfunction "1_1") (pintype "passive"))
    )
    (net (code "82") (name "Net-(DS5-A)") (class "Default")
      (node (ref "DS5") (pin "1") (pinfunction "A_1") (pintype "passive"))
      (node (ref "R11") (pin "1") (pinfunction "1_1") (pintype "passive"))
    )
    (net (code "83") (name "Net-(DS6-A)") (class "Default")
      (node (ref "DS6") (pin "1") (pinfunction "A_1") (pintype "passive"))
      (node (ref "R12") (pin "1") (pinfunction "1_1") (pintype "passive"))
    )
    (net (code "84") (name "Net-(J18-Pad3)") (class "Default")
      (node (ref "J18") (pin "3") (pinfunction "3_3") (pintype "passive"))
      (node (ref "W27") (pin "1") (pinfunction "1_1") (pintype "passive"))
      (node (ref "W28") (pin "1") (pinfunction "1_1") (pintype "passive"))
    )
    (net (code "85") (name "Net-(J22-Pad3)") (class "Default")
      (node (ref "J22") (pin "3") (pinfunction "3_3") (pintype "passive"))
      (node (ref "W12") (pin "1") (pinfunction "1_1") (pintype "passive"))
      (node (ref "W8") (pin "1") (pinfunction "1_1") (pintype "passive"))
    )
    (net (code "86") (name "Net-(J23-Pad3)") (class "Default")
      (node (ref "J23") (pin "3") (pinfunction "3_3") (pintype "passive"))
      (node (ref "W13") (pin "1") (pinfunction "1_1") (pintype "passive"))
      (node (ref "W9") (pin "1") (pinfunction "1_1") (pintype "passive"))
    )
    (net (code "87") (name "Net-(J24-Pad3)") (class "Default")
      (node (ref "J24") (pin "3") (pinfunction "3_3") (pintype "passive"))
      (node (ref "W10") (pin "1") (pinfunction "1_1") (pintype "passive"))
      (node (ref "W14") (pin "1") (pinfunction "1_1") (pintype "passive"))
    )
    (net (code "88") (name "Net-(U1-A0)") (class "Default")
      (node (ref "U1") (pin "15") (pinfunction "A0_15") (pintype "input"))
      (node (ref "W5") (pin "1") (pinfunction "1_1") (pintype "passive"))
      (node (ref "W6") (pin "2") (pinfunction "2_2") (pintype "passive"))
    )
    (net (code "89") (name "Net-(U1-A1)") (class "Default")
      (node (ref "U1") (pin "16") (pinfunction "A1_16") (pintype "input"))
      (node (ref "W3") (pin "1") (pinfunction "1_1") (pintype "passive"))
      (node (ref "W4") (pin "2") (pinfunction "2_2") (pintype "passive"))
    )
    (net (code "90") (name "Net-(U1-A2)") (class "Default")
      (node (ref "U1") (pin "17") (pinfunction "A2_17") (pintype "input"))
      (node (ref "W1") (pin "1") (pinfunction "1_1") (pintype "passive"))
      (node (ref "W2") (pin "2") (pinfunction "2_2") (pintype "passive"))
    )
    (net (code "91") (name "Net-(U1-INTA)") (class "Default")
      (node (ref "R1") (pin "1") (pinfunction "1_1") (pintype "passive"))
      (node (ref "U1") (pin "20") (pinfunction "INTA_20") (pintype "open_collector"))
    )
    (net (code "92") (name "Net-(U1-INTB)") (class "Default")
      (node (ref "R2") (pin "1") (pinfunction "1_1") (pintype "passive"))
      (node (ref "U1") (pin "19") (pinfunction "INTB_19") (pintype "open_collector"))
    )
    (net (code "93") (name "Net-(U3-3V3)") (class "Default")
      (node (ref "C1") (pin "1") (pinfunction "1_1") (pintype "passive"))
      (node (ref "C2") (pin "1") (pinfunction "1_1") (pintype "passive"))
      (node (ref "P1") (pin "1") (pinfunction "1_1") (pintype "passive"))
      (node (ref "R5") (pin "2") (pinfunction "2_2") (pintype "passive"))
      (node (ref "R6") (pin "2") (pinfunction "2_2") (pintype "passive"))
      (node (ref "S1") (pin "1") (pinfunction "1_1") (pintype "passive"))
      (node (ref "U3") (pin "2") (pinfunction "3V3_2") (pintype "bidirectional"))
    )
    (net (code "94") (name "unconnected-(U1-NC-Pad11)") (class "Default")
      (node (ref "U1") (pin "11") (pinfunction "NC_11") (pintype "passive+no_connect"))
    )
    (net (code "95") (name "unconnected-(U1-NC-Pad14)") (class "Default")
      (node (ref "U1") (pin "14") (pinfunction "NC_14") (pintype "passive+no_connect"))
    )
    (net (code "96") (name "unconnected-(U2-ALERT{slash}RDY-Pad2)") (class "Default")
      (node (ref "U2") (pin "2") (pinfunction "ALERT/RDY_2") (pintype "open_collector+no_connect"))
    )
    (net (code "97") (name "unconnected-(U3-IO3-Pad15)") (class "Default")
      (node (ref "U3") (pin "15") (pinfunction "IO3_15") (pintype "bidirectional+no_connect"))
    )
  )
)
